# imu.net
KiCad netlist of a schematic drawn in EasyEDA Pro
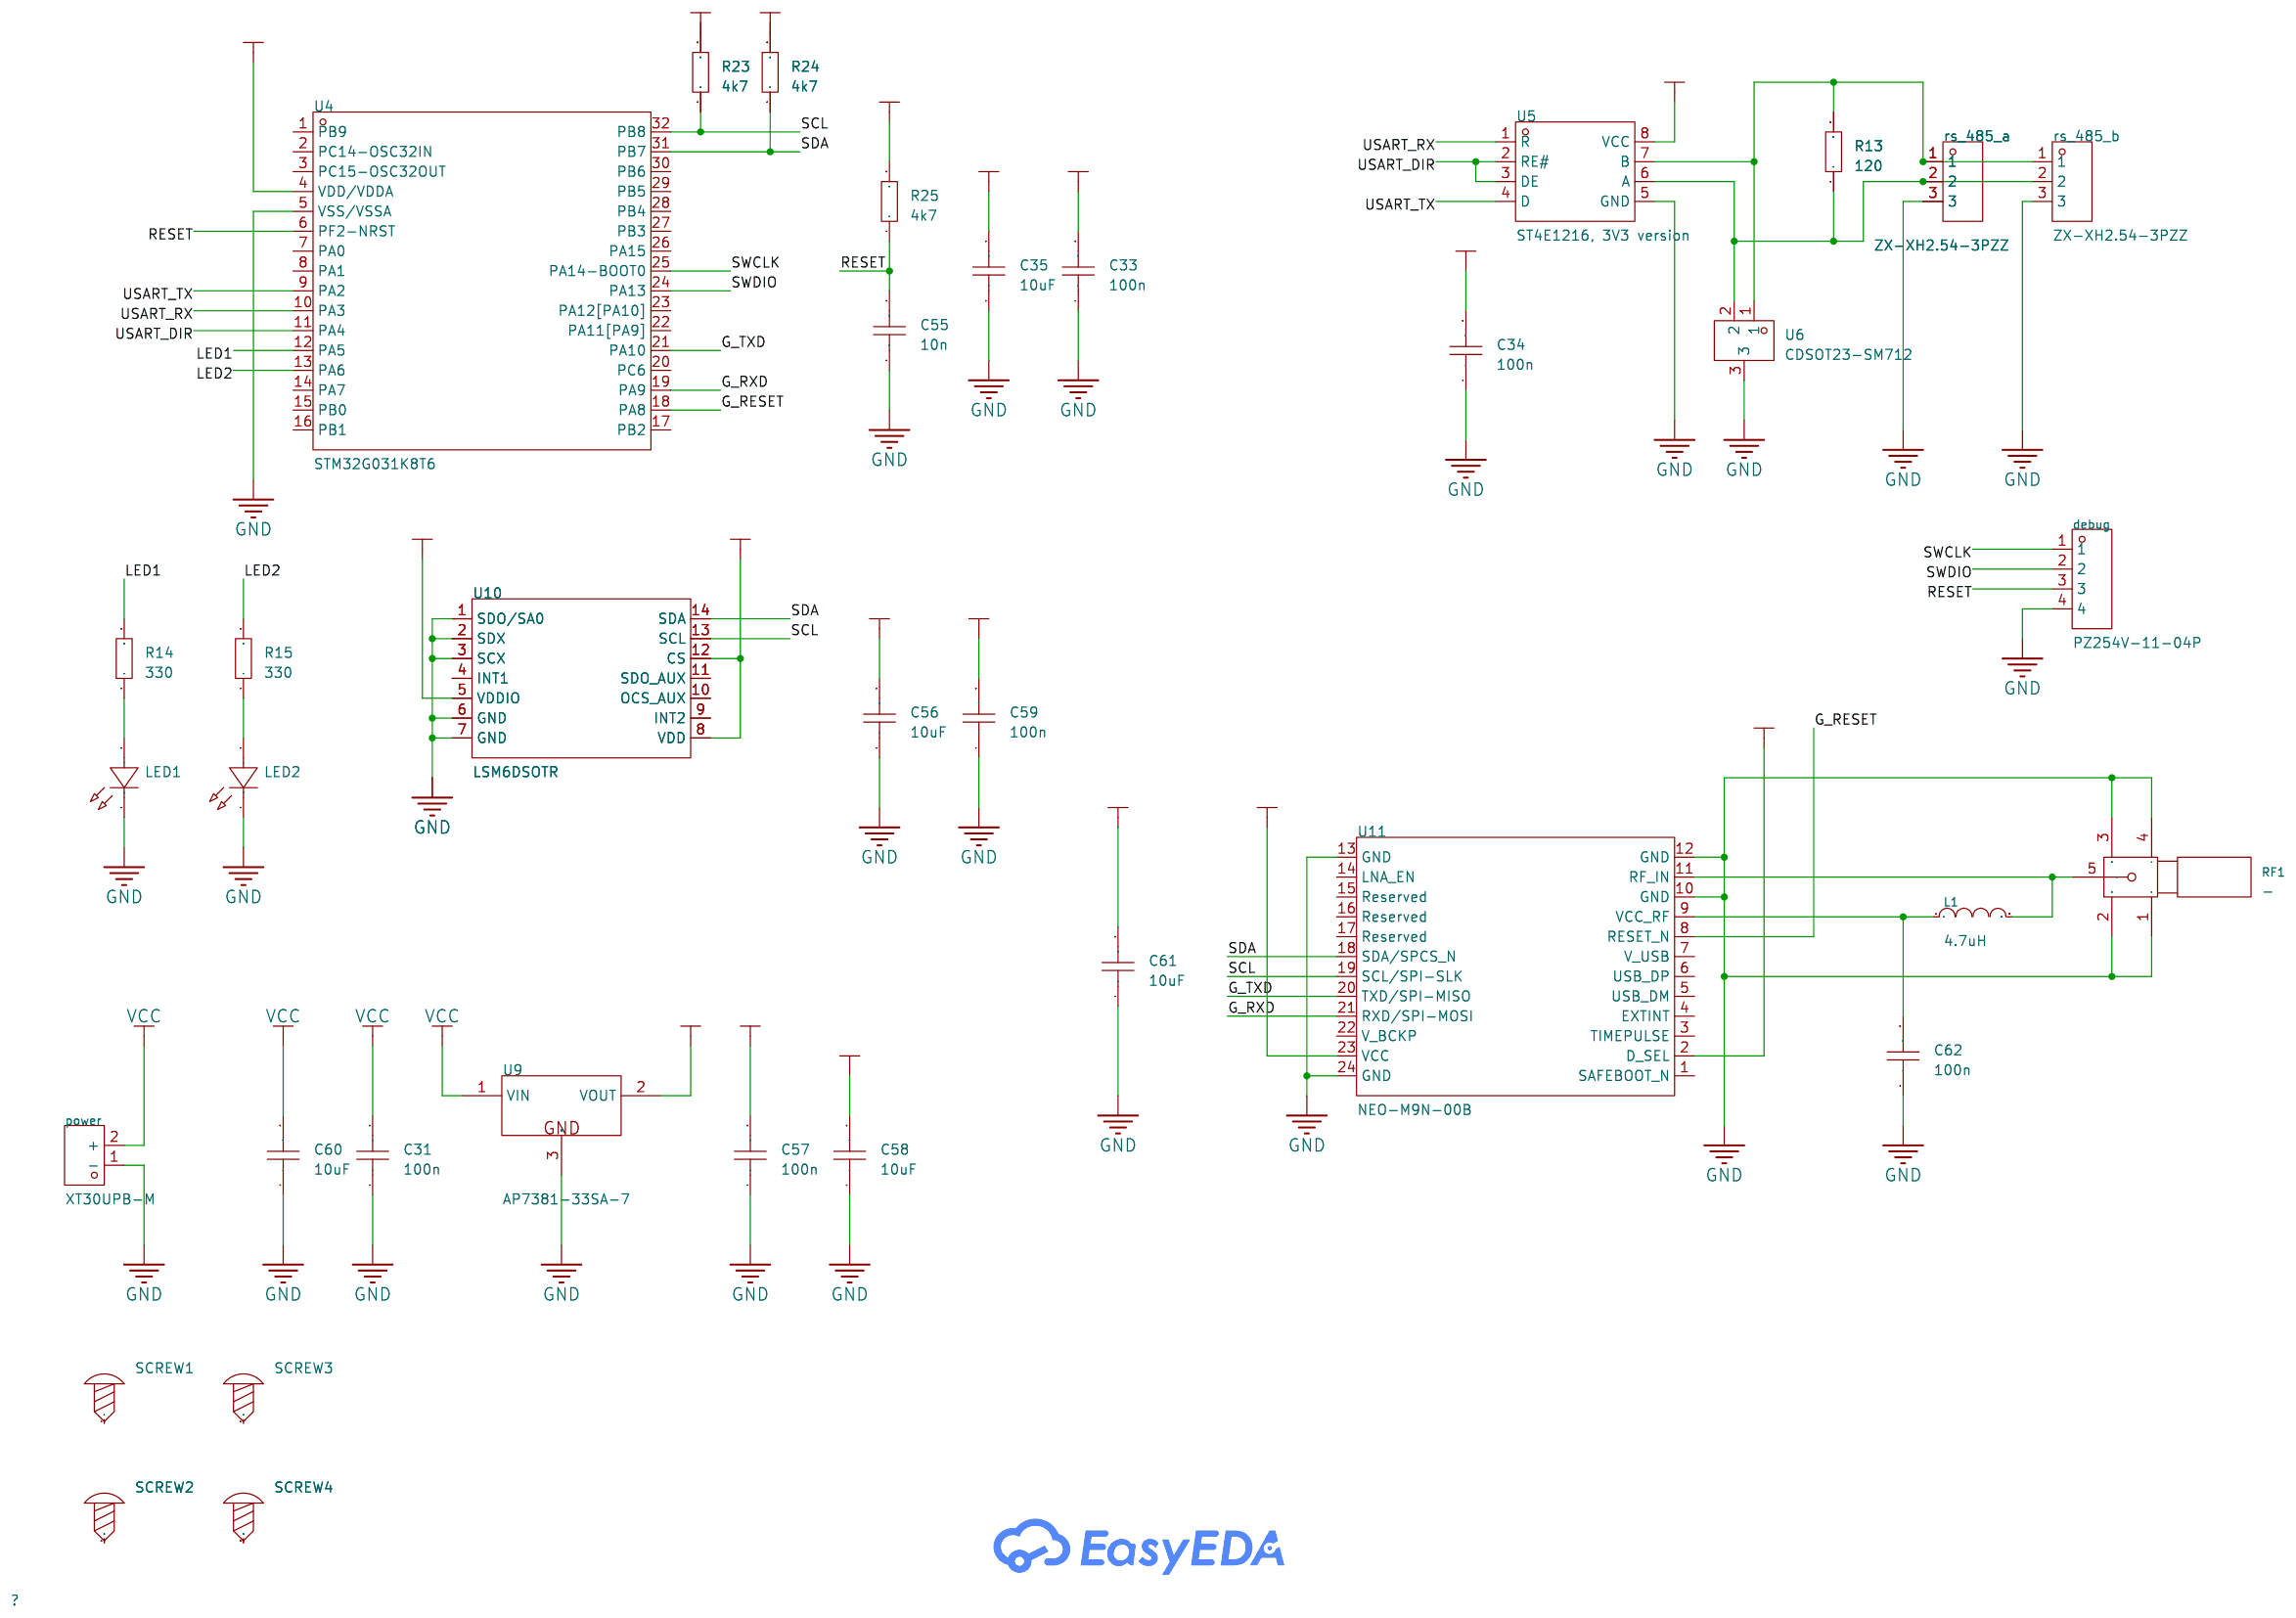
[diagram p0: schematic sheet]

(export (version "E")
  (design (tool "Eeschema 10.0.6"))
  (components
    (comp (ref "C31")
      (value "10uF")
      (footprint "easyedapro:C0805")
      (description "Capacitance:10uF Tolerance:±10% Tolerance:±10% Voltage Rating:25V Temperature Coefficient:X5R")
      (fields
        (field (name "Manufacturer Part") "CL21A106KAYNNNE")
        (field (name "Manufacturer") "SAMSUNG(三星)")
      )
      (libsource (lib "easyedapro") (part "CL21A106KAYNNNE"))
    )
    (comp (ref "C33")
      (value "10uF")
      (footprint "easyedapro:C0805")
      (description "Capacitance:10uF Tolerance:±10% Tolerance:±10% Voltage Rating:25V Temperature Coefficient:X5R")
      (fields
        (field (name "Manufacturer Part") "CL21A106KAYNNNE")
        (field (name "Manufacturer") "SAMSUNG(三星)")
      )
      (libsource (lib "easyedapro") (part "CL21A106KAYNNNE"))
    )
    (comp (ref "C34")
      (value "10uF")
      (footprint "easyedapro:C0805")
      (description "Capacitance:10uF Tolerance:±10% Tolerance:±10% Voltage Rating:25V Temperature Coefficient:X5R")
      (fields
        (field (name "Manufacturer Part") "CL21A106KAYNNNE")
        (field (name "Manufacturer") "SAMSUNG(三星)")
      )
      (libsource (lib "easyedapro") (part "CL21A106KAYNNNE"))
    )
    (comp (ref "C35")
      (value "10uF")
      (footprint "easyedapro:C0805")
      (description "Capacitance:10uF Tolerance:±10% Tolerance:±10% Voltage Rating:25V Temperature Coefficient:X5R")
      (fields
        (field (name "Manufacturer Part") "CL21A106KAYNNNE")
        (field (name "Manufacturer") "SAMSUNG(三星)")
      )
      (libsource (lib "easyedapro") (part "CL21A106KAYNNNE"))
    )
    (comp (ref "C55")
      (value "10uF")
      (footprint "easyedapro:C0805")
      (description "Capacitance:10uF Tolerance:±10% Tolerance:±10% Voltage Rating:25V Temperature Coefficient:X5R")
      (fields
        (field (name "Manufacturer Part") "CL21A106KAYNNNE")
        (field (name "Manufacturer") "SAMSUNG(三星)")
      )
      (libsource (lib "easyedapro") (part "CL21A106KAYNNNE"))
    )
    (comp (ref "C56")
      (value "10uF")
      (footprint "easyedapro:C0805")
      (description "Capacitance:10uF Tolerance:±10% Tolerance:±10% Voltage Rating:25V Temperature Coefficient:X5R")
      (fields
        (field (name "Manufacturer Part") "CL21A106KAYNNNE")
        (field (name "Manufacturer") "SAMSUNG(三星)")
      )
      (libsource (lib "easyedapro") (part "CL21A106KAYNNNE"))
    )
    (comp (ref "C57")
      (value "10uF")
      (footprint "easyedapro:C0805")
      (description "Capacitance:10uF Tolerance:±10% Tolerance:±10% Voltage Rating:25V Temperature Coefficient:X5R")
      (fields
        (field (name "Manufacturer Part") "CL21A106KAYNNNE")
        (field (name "Manufacturer") "SAMSUNG(三星)")
      )
      (libsource (lib "easyedapro") (part "CL21A106KAYNNNE"))
    )
    (comp (ref "C58")
      (value "10uF")
      (footprint "easyedapro:C0805")
      (description "Capacitance:10uF Tolerance:±10% Tolerance:±10% Voltage Rating:25V Temperature Coefficient:X5R")
      (fields
        (field (name "Manufacturer Part") "CL21A106KAYNNNE")
        (field (name "Manufacturer") "SAMSUNG(三星)")
      )
      (libsource (lib "easyedapro") (part "CL21A106KAYNNNE"))
    )
    (comp (ref "C59")
      (value "10uF")
      (footprint "easyedapro:C0805")
      (description "Capacitance:10uF Tolerance:±10% Tolerance:±10% Voltage Rating:25V Temperature Coefficient:X5R")
      (fields
        (field (name "Manufacturer Part") "CL21A106KAYNNNE")
        (field (name "Manufacturer") "SAMSUNG(三星)")
      )
      (libsource (lib "easyedapro") (part "CL21A106KAYNNNE"))
    )
    (comp (ref "C60")
      (value "10uF")
      (footprint "easyedapro:C0805")
      (description "Capacitance:10uF Tolerance:±10% Tolerance:±10% Voltage Rating:25V Temperature Coefficient:X5R")
      (fields
        (field (name "Manufacturer Part") "CL21A106KAYNNNE")
        (field (name "Manufacturer") "SAMSUNG(三星)")
      )
      (libsource (lib "easyedapro") (part "CL21A106KAYNNNE"))
    )
    (comp (ref "C61")
      (value "10uF")
      (footprint "easyedapro:C0805")
      (description "Capacitance:10uF Tolerance:±10% Tolerance:±10% Voltage Rating:25V Temperature Coefficient:X5R")
      (fields
        (field (name "Manufacturer Part") "CL21A106KAYNNNE")
        (field (name "Manufacturer") "SAMSUNG(三星)")
      )
      (libsource (lib "easyedapro") (part "CL21A106KAYNNNE"))
    )
    (comp (ref "C62")
      (value "10uF")
      (footprint "easyedapro:C0805")
      (description "Capacitance:10uF Tolerance:±10% Tolerance:±10% Voltage Rating:25V Temperature Coefficient:X5R")
      (fields
        (field (name "Manufacturer Part") "CL21A106KAYNNNE")
        (field (name "Manufacturer") "SAMSUNG(三星)")
      )
      (libsource (lib "easyedapro") (part "CL21A106KAYNNNE"))
    )
    (comp (ref "debug")
      (value "PZ254V-11-04P")
      (footprint "easyedapro:HDR-TH_4P-P2.54-V-M")
      (fields (field (name "Manufacturer") "XFCN(兴飞)"))
      (libsource (lib "easyedapro") (part "PZ254V-11-04P_C2691448"))
    )
    (comp (ref "L1")
      (value "4.7uH")
      (footprint "easyedapro:L0805")
      (fields (field (name "Manufacturer Part") "LQM21PN4R7MGRD") (field (name "Manufacturer") "muRata(村田)"))
      (libsource (lib "easyedapro") (part "LQM21PN4R7MGRD"))
    )
    (comp (ref "LED1")
      (value "P2-1206RTCS2-0.9T-F")
      (footprint "easyedapro:LED-SMD_L3.2-W1.6-P2-1206RTCS2-0.9T-F")
      (fields (field (name "Manufacturer") "TUOZHAN(拓展光电)"))
      (libsource (lib "easyedapro") (part "P2-1206RTCS2-0.9T-F"))
    )
    (comp (ref "LED2")
      (value "P2-1206RTCS2-0.9T-F")
      (footprint "easyedapro:LED-SMD_L3.2-W1.6-P2-1206RTCS2-0.9T-F")
      (fields (field (name "Manufacturer") "TUOZHAN(拓展光电)"))
      (libsource (lib "easyedapro") (part "P2-1206RTCS2-0.9T-F"))
    )
    (comp (ref "power")
      (value "XT30UPB-M")
      (footprint "easyedapro:CONN-TH_XT30UPB-M")
      (fields (field (name "Manufacturer") "AMASS(艾迈斯)"))
      (libsource (lib "easyedapro") (part "XT30UPB-M"))
    )
    (comp (ref "R13")
      (value "10kΩ")
      (footprint "easyedapro:R0805")
      (fields
        (field (name "Manufacturer Part") "0805W8F1002T5E")
        (field (name "Manufacturer") "UNI-ROYAL(厚声)")
      )
      (libsource (lib "easyedapro") (part "0805W8F1002T5E"))
    )
    (comp (ref "R14")
      (value "10kΩ")
      (footprint "easyedapro:R0805")
      (fields
        (field (name "Manufacturer Part") "0805W8F1002T5E")
        (field (name "Manufacturer") "UNI-ROYAL(厚声)")
      )
      (libsource (lib "easyedapro") (part "0805W8F1002T5E"))
    )
    (comp (ref "R15")
      (value "10kΩ")
      (footprint "easyedapro:R0805")
      (fields
        (field (name "Manufacturer Part") "0805W8F1002T5E")
        (field (name "Manufacturer") "UNI-ROYAL(厚声)")
      )
      (libsource (lib "easyedapro") (part "0805W8F1002T5E"))
    )
    (comp (ref "R23")
      (value "10kΩ")
      (footprint "easyedapro:R0805")
      (fields
        (field (name "Manufacturer Part") "0805W8F1002T5E")
        (field (name "Manufacturer") "UNI-ROYAL(厚声)")
      )
      (libsource (lib "easyedapro") (part "0805W8F1002T5E"))
    )
    (comp (ref "R24")
      (value "10kΩ")
      (footprint "easyedapro:R0805")
      (fields
        (field (name "Manufacturer Part") "0805W8F1002T5E")
        (field (name "Manufacturer") "UNI-ROYAL(厚声)")
      )
      (libsource (lib "easyedapro") (part "0805W8F1002T5E"))
    )
    (comp (ref "R25")
      (value "10kΩ")
      (footprint "easyedapro:R0805")
      (fields
        (field (name "Manufacturer Part") "0805W8F1002T5E")
        (field (name "Manufacturer") "UNI-ROYAL(厚声)")
      )
      (libsource (lib "easyedapro") (part "0805W8F1002T5E"))
    )
    (comp (ref "RF1")
      (value "-")
      (footprint "easyedapro:SMA-TH_BWSMA-KWE-Z001")
      (fields
        (field (name "Manufacturer Part") "BWSMA-KWE-Z001")
        (field (name "Manufacturer") "BAT WIRELESS(蝙蝠无线)")
      )
      (libsource (lib "easyedapro") (part "BWSMA-KWE-Z001"))
    )
    (comp (ref "rs_485_a")
      (value "ZX-XH2.54-3PZZ")
      (footprint "easyedapro:CONN-TH_3P-P2.54_2501S-3P")
      (fields (field (name "Manufacturer") "Megastar(兆星)"))
      (libsource (lib "easyedapro") (part "ZX-XH2.54-3PZZ"))
    )
    (comp (ref "rs_485_b")
      (value "ZX-XH2.54-3PZZ")
      (footprint "easyedapro:CONN-TH_3P-P2.54_2501S-3P")
      (fields (field (name "Manufacturer") "Megastar(兆星)"))
      (libsource (lib "easyedapro") (part "ZX-XH2.54-3PZZ"))
    )
    (comp (ref "SCREW1")
      (value "~")
      (footprint "easyedapro:Screw-Hole-M3")
      (libsource (lib "easyedapro") (part "Screw-Hole"))
    )
    (comp (ref "SCREW2")
      (value "~")
      (footprint "easyedapro:Screw-Hole-M3")
      (libsource (lib "easyedapro") (part "Screw-Hole"))
    )
    (comp (ref "SCREW3")
      (value "~")
      (footprint "easyedapro:Screw-Hole-M3")
      (libsource (lib "easyedapro") (part "Screw-Hole"))
    )
    (comp (ref "SCREW4")
      (value "~")
      (footprint "easyedapro:Screw-Hole-M3")
      (libsource (lib "easyedapro") (part "Screw-Hole"))
    )
    (comp (ref "U4")
      (value "STM32G031K8T6")
      (footprint "easyedapro:LQFP-32_L7.0-W7.0-P0.80-LS9.0-BL")
      (fields (field (name "Manufacturer") "ST(意法半导体)"))
      (libsource (lib "easyedapro") (part "STM32G031K8T6"))
    )
    (comp (ref "U5")
      (value "ST4E1216, 3V3 version")
      (footprint "easyedapro:NSOIC-8_L4.9-W3.9-P1.27-LS6.1-BL")
      (fields (field (name "Manufacturer") "TI(德州仪器)"))
      (libsource (lib "easyedapro") (part "THVD1510DR"))
    )
    (comp (ref "U6")
      (value "CDSOT23-SM712")
      (footprint "easyedapro:SOT-23-3_L2.9-W1.3-P0.95-LS2.4-BR")
      (fields (field (name "Manufacturer") "TECH PUBLIC(台舟)"))
      (libsource (lib "easyedapro") (part "CDSOT23-SM712_C5122012"))
    )
    (comp (ref "U9")
      (value "AP7381-33SA-7")
      (footprint "easyedapro:SOT-23-3_L2.9-W1.3-P1.90-LS2.4-BR")
      (fields (field (name "Manufacturer") "DIODES(美台)"))
      (libsource (lib "easyedapro") (part "AP7381-33SA-7"))
    )
    (comp (ref "U10")
      (value "LSM6DSOTR")
      (footprint "easyedapro:LGA-14_L3.0-W2.5-P0.50-TL")
      (fields (field (name "Manufacturer") "ST(意法半导体)"))
      (libsource (lib "easyedapro") (part "LSM6DSOTR"))
    )
    (comp (ref "U11")
      (value "NEO-M9N-00B")
      (footprint "easyedapro:GPSM-SMD_24P-L16.0-W12.2-P1.10-BL")
      (fields (field (name "Manufacturer") "U-BLOX"))
      (libsource (lib "easyedapro") (part "NEO-M9N-00B"))
    )
  )
  (nets
    (net (code "1") (name "+3V3") (class "Default")
      (node (ref "C33") (pin "2") (pinfunction "2_2") (pintype "unspecified"))
      (node (ref "C34") (pin "2") (pinfunction "2_2") (pintype "unspecified"))
      (node (ref "C35") (pin "2") (pinfunction "2_2") (pintype "unspecified"))
      (node (ref "C56") (pin "2") (pinfunction "2_2") (pintype "unspecified"))
      (node (ref "C57") (pin "2") (pinfunction "2_2") (pintype "unspecified"))
      (node (ref "C58") (pin "2") (pinfunction "2_2") (pintype "unspecified"))
      (node (ref "C59") (pin "2") (pinfunction "2_2") (pintype "unspecified"))
      (node (ref "C61") (pin "2") (pinfunction "2_2") (pintype "unspecified"))
      (node (ref "R23") (pin "2") (pinfunction "2_2") (pintype "input"))
      (node (ref "R24") (pin "2") (pinfunction "2_2") (pintype "input"))
      (node (ref "R25") (pin "2") (pinfunction "2_2") (pintype "input"))
      (node (ref "U10") (pin "12") (pinfunction "CS_12") (pintype "unspecified"))
      (node (ref "U10") (pin "5") (pinfunction "VDDIO_5") (pintype "unspecified"))
      (node (ref "U10") (pin "8") (pinfunction "VDD_8") (pintype "unspecified"))
      (node (ref "U11") (pin "2") (pinfunction "D_SEL_2") (pintype "unspecified"))
      (node (ref "U11") (pin "23") (pinfunction "VCC_23") (pintype "unspecified"))
      (node (ref "U4") (pin "4") (pinfunction "VDD/VDDA_4") (pintype "unspecified"))
      (node (ref "U5") (pin "8") (pinfunction "VCC_8") (pintype "unspecified"))
      (node (ref "U9") (pin "2") (pinfunction "VOUT_2") (pintype "unspecified"))
    )
    (net (code "2") (name "/G_RESET") (class "Default")
      (node (ref "U11") (pin "8") (pinfunction "RESET_N_8") (pintype "unspecified"))
      (node (ref "U4") (pin "18") (pinfunction "PA8_18") (pintype "unspecified"))
    )
    (net (code "3") (name "/G_RXD") (class "Default")
      (node (ref "U11") (pin "21") (pinfunction "RXD/SPI-MOSI_21") (pintype "unspecified"))
      (node (ref "U4") (pin "19") (pinfunction "PA9_19") (pintype "unspecified"))
    )
    (net (code "4") (name "/G_TXD") (class "Default")
      (node (ref "U11") (pin "20") (pinfunction "TXD/SPI-MISO_20") (pintype "unspecified"))
      (node (ref "U4") (pin "21") (pinfunction "PA10_21") (pintype "unspecified"))
    )
    (net (code "5") (name "/LED1") (class "Default")
      (node (ref "R14") (pin "2") (pinfunction "2_2") (pintype "input"))
      (node (ref "U4") (pin "12") (pinfunction "PA5_12") (pintype "unspecified"))
    )
    (net (code "6") (name "/LED2") (class "Default")
      (node (ref "R15") (pin "2") (pinfunction "2_2") (pintype "input"))
      (node (ref "U4") (pin "13") (pinfunction "PA6_13") (pintype "unspecified"))
    )
    (net (code "7") (name "/RESET") (class "Default")
      (node (ref "C55") (pin "2") (pinfunction "2_2") (pintype "unspecified"))
      (node (ref "R25") (pin "1") (pinfunction "1_1") (pintype "input"))
      (node (ref "U4") (pin "6") (pinfunction "PF2-NRST_6") (pintype "unspecified"))
      (node (ref "debug") (pin "3") (pinfunction "3_3") (pintype "input"))
    )
    (net (code "8") (name "/SCL") (class "Default")
      (node (ref "R23") (pin "1") (pinfunction "1_1") (pintype "input"))
      (node (ref "U10") (pin "13") (pinfunction "SCL_13") (pintype "unspecified"))
      (node (ref "U11") (pin "19") (pinfunction "SCL/SPI-SLK_19") (pintype "unspecified"))
      (node (ref "U4") (pin "32") (pinfunction "PB8_32") (pintype "unspecified"))
    )
    (net (code "9") (name "/SDA") (class "Default")
      (node (ref "R24") (pin "1") (pinfunction "1_1") (pintype "input"))
      (node (ref "U10") (pin "14") (pinfunction "SDA_14") (pintype "unspecified"))
      (node (ref "U11") (pin "18") (pinfunction "SDA/SPCS_N_18") (pintype "unspecified"))
      (node (ref "U4") (pin "31") (pinfunction "PB7_31") (pintype "unspecified"))
    )
    (net (code "10") (name "/SWCLK") (class "Default")
      (node (ref "U4") (pin "25") (pinfunction "PA14-BOOT0_25") (pintype "unspecified"))
      (node (ref "debug") (pin "1") (pinfunction "1_1") (pintype "input"))
    )
    (net (code "11") (name "/SWDIO") (class "Default")
      (node (ref "U4") (pin "24") (pinfunction "PA13_24") (pintype "unspecified"))
      (node (ref "debug") (pin "2") (pinfunction "2_2") (pintype "input"))
    )
    (net (code "12") (name "/USART_DIR") (class "Default")
      (node (ref "U4") (pin "11") (pinfunction "PA4_11") (pintype "unspecified"))
      (node (ref "U5") (pin "2") (pinfunction "RE#_2") (pintype "unspecified"))
      (node (ref "U5") (pin "3") (pinfunction "DE_3") (pintype "unspecified"))
    )
    (net (code "13") (name "/USART_RX") (class "Default")
      (node (ref "U4") (pin "10") (pinfunction "PA3_10") (pintype "unspecified"))
      (node (ref "U5") (pin "1") (pinfunction "R_1") (pintype "unspecified"))
    )
    (net (code "14") (name "/USART_TX") (class "Default")
      (node (ref "U4") (pin "9") (pinfunction "PA2_9") (pintype "unspecified"))
      (node (ref "U5") (pin "4") (pinfunction "D_4") (pintype "unspecified"))
    )
    (net (code "15") (name "GND") (class "Default")
      (node (ref "C31") (pin "1") (pinfunction "1_1") (pintype "unspecified"))
      (node (ref "C33") (pin "1") (pinfunction "1_1") (pintype "unspecified"))
      (node (ref "C34") (pin "1") (pinfunction "1_1") (pintype "unspecified"))
      (node (ref "C35") (pin "1") (pinfunction "1_1") (pintype "unspecified"))
      (node (ref "C55") (pin "1") (pinfunction "1_1") (pintype "unspecified"))
      (node (ref "C56") (pin "1") (pinfunction "1_1") (pintype "unspecified"))
      (node (ref "C57") (pin "1") (pinfunction "1_1") (pintype "unspecified"))
      (node (ref "C58") (pin "1") (pinfunction "1_1") (pintype "unspecified"))
      (node (ref "C59") (pin "1") (pinfunction "1_1") (pintype "unspecified"))
      (node (ref "C60") (pin "1") (pinfunction "1_1") (pintype "unspecified"))
      (node (ref "C61") (pin "1") (pinfunction "1_1") (pintype "unspecified"))
      (node (ref "C62") (pin "1") (pinfunction "1_1") (pintype "unspecified"))
      (node (ref "LED1") (pin "1") (pinfunction "C_1") (pintype "unspecified"))
      (node (ref "LED2") (pin "1") (pinfunction "C_1") (pintype "unspecified"))
      (node (ref "RF1") (pin "1") (pinfunction "1_1") (pintype "input"))
      (node (ref "RF1") (pin "2") (pinfunction "2_2") (pintype "input"))
      (node (ref "RF1") (pin "3") (pinfunction "3_3") (pintype "input"))
      (node (ref "RF1") (pin "4") (pinfunction "4_4") (pintype "input"))
      (node (ref "U10") (pin "1") (pinfunction "SDO/SA0_1") (pintype "unspecified"))
      (node (ref "U10") (pin "2") (pinfunction "SDX_2") (pintype "unspecified"))
      (node (ref "U10") (pin "3") (pinfunction "SCX_3") (pintype "unspecified"))
      (node (ref "U10") (pin "6") (pinfunction "GND_6") (pintype "unspecified"))
      (node (ref "U10") (pin "7") (pinfunction "GND_7") (pintype "unspecified"))
      (node (ref "U11") (pin "10") (pinfunction "GND_10") (pintype "unspecified"))
      (node (ref "U11") (pin "12") (pinfunction "GND_12") (pintype "unspecified"))
      (node (ref "U11") (pin "13") (pinfunction "GND_13") (pintype "unspecified"))
      (node (ref "U11") (pin "24") (pinfunction "GND_24") (pintype "unspecified"))
      (node (ref "U4") (pin "5") (pinfunction "VSS/VSSA_5") (pintype "unspecified"))
      (node (ref "U5") (pin "5") (pinfunction "GND_5") (pintype "unspecified"))
      (node (ref "U6") (pin "3") (pinfunction "3_3") (pintype "unspecified"))
      (node (ref "U9") (pin "3") (pinfunction "GND_3") (pintype "unspecified"))
      (node (ref "debug") (pin "4") (pinfunction "4_4") (pintype "input"))
      (node (ref "power") (pin "1") (pinfunction "-_1") (pintype "input"))
      (node (ref "rs_485_a") (pin "3") (pinfunction "3_3") (pintype "unspecified"))
      (node (ref "rs_485_b") (pin "3") (pinfunction "3_3") (pintype "unspecified"))
    )
    (net (code "16") (name "Net-(LED1-A)") (class "Default")
      (node (ref "LED1") (pin "2") (pinfunction "A_2") (pintype "unspecified"))
      (node (ref "R14") (pin "1") (pinfunction "1_1") (pintype "input"))
    )
    (net (code "17") (name "Net-(LED2-A)") (class "Default")
      (node (ref "LED2") (pin "2") (pinfunction "A_2") (pintype "unspecified"))
      (node (ref "R15") (pin "1") (pinfunction "1_1") (pintype "input"))
    )
    (net (code "18") (name "Net-(U5-A)") (class "Default")
      (node (ref "R13") (pin "1") (pinfunction "1_1") (pintype "input"))
      (node (ref "U5") (pin "6") (pinfunction "A_6") (pintype "unspecified"))
      (node (ref "U6") (pin "2") (pinfunction "2_2") (pintype "unspecified"))
      (node (ref "rs_485_a") (pin "2") (pinfunction "2_2") (pintype "unspecified"))
      (node (ref "rs_485_b") (pin "2") (pinfunction "2_2") (pintype "unspecified"))
    )
    (net (code "19") (name "Net-(U5-B)") (class "Default")
      (node (ref "R13") (pin "2") (pinfunction "2_2") (pintype "input"))
      (node (ref "U5") (pin "7") (pinfunction "B_7") (pintype "unspecified"))
      (node (ref "U6") (pin "1") (pinfunction "1_1") (pintype "unspecified"))
      (node (ref "rs_485_a") (pin "1") (pinfunction "1_1") (pintype "unspecified"))
      (node (ref "rs_485_b") (pin "1") (pinfunction "1_1") (pintype "unspecified"))
    )
    (net (code "20") (name "Net-(U11-RF_IN)") (class "Default")
      (node (ref "L1") (pin "2") (pinfunction "2_2") (pintype "input"))
      (node (ref "RF1") (pin "5") (pinfunction "5_5") (pintype "input"))
      (node (ref "U11") (pin "11") (pinfunction "RF_IN_11") (pintype "unspecified"))
    )
    (net (code "21") (name "Net-(U11-VCC_RF)") (class "Default")
      (node (ref "C62") (pin "2") (pinfunction "2_2") (pintype "unspecified"))
      (node (ref "L1") (pin "1") (pinfunction "1_1") (pintype "input"))
      (node (ref "U11") (pin "9") (pinfunction "VCC_RF_9") (pintype "unspecified"))
    )
    (net (code "22") (name "VCC") (class "Default")
      (node (ref "C31") (pin "2") (pinfunction "2_2") (pintype "unspecified"))
      (node (ref "C60") (pin "2") (pinfunction "2_2") (pintype "unspecified"))
      (node (ref "U9") (pin "1") (pinfunction "VIN_1") (pintype "unspecified"))
      (node (ref "power") (pin "2") (pinfunction "+_2") (pintype "input"))
    )
    (net (code "23") (name "unconnected-(SCREW1-Pad1)") (class "Default")
      (node (ref "SCREW1") (pin "1") (pinfunction "1_1") (pintype "input"))
    )
    (net (code "24") (name "unconnected-(SCREW2-Pad1)") (class "Default")
      (node (ref "SCREW2") (pin "1") (pinfunction "1_1") (pintype "input"))
    )
    (net (code "25") (name "unconnected-(SCREW3-Pad1)") (class "Default")
      (node (ref "SCREW3") (pin "1") (pinfunction "1_1") (pintype "input"))
    )
    (net (code "26") (name "unconnected-(SCREW4-Pad1)") (class "Default")
      (node (ref "SCREW4") (pin "1") (pinfunction "1_1") (pintype "input"))
    )
    (net (code "27") (name "unconnected-(U4-PA0-Pad7)") (class "Default")
      (node (ref "U4") (pin "7") (pinfunction "PA0_7") (pintype "unspecified"))
    )
    (net (code "28") (name "unconnected-(U4-PA1-Pad8)") (class "Default")
      (node (ref "U4") (pin "8") (pinfunction "PA1_8") (pintype "unspecified"))
    )
    (net (code "29") (name "unconnected-(U4-PA7-Pad14)") (class "Default")
      (node (ref "U4") (pin "14") (pinfunction "PA7_14") (pintype "unspecified"))
    )
    (net (code "30") (name "unconnected-(U4-PA11[PA9]-Pad22)") (class "Default")
      (node (ref "U4") (pin "22") (pinfunction "PA11[PA9]_22") (pintype "unspecified"))
    )
    (net (code "31") (name "unconnected-(U4-PA12[PA10]-Pad23)") (class "Default")
      (node (ref "U4") (pin "23") (pinfunction "PA12[PA10]_23") (pintype "unspecified"))
    )
    (net (code "32") (name "unconnected-(U4-PA15-Pad26)") (class "Default")
      (node (ref "U4") (pin "26") (pinfunction "PA15_26") (pintype "unspecified"))
    )
    (net (code "33") (name "unconnected-(U4-PB0-Pad15)") (class "Default")
      (node (ref "U4") (pin "15") (pinfunction "PB0_15") (pintype "unspecified"))
    )
    (net (code "34") (name "unconnected-(U4-PB1-Pad16)") (class "Default")
      (node (ref "U4") (pin "16") (pinfunction "PB1_16") (pintype "unspecified"))
    )
    (net (code "35") (name "unconnected-(U4-PB2-Pad17)") (class "Default")
      (node (ref "U4") (pin "17") (pinfunction "PB2_17") (pintype "unspecified"))
    )
    (net (code "36") (name "unconnected-(U4-PB3-Pad27)") (class "Default")
      (node (ref "U4") (pin "27") (pinfunction "PB3_27") (pintype "unspecified"))
    )
    (net (code "37") (name "unconnected-(U4-PB4-Pad28)") (class "Default")
      (node (ref "U4") (pin "28") (pinfunction "PB4_28") (pintype "unspecified"))
    )
    (net (code "38") (name "unconnected-(U4-PB5-Pad29)") (class "Default")
      (node (ref "U4") (pin "29") (pinfunction "PB5_29") (pintype "unspecified"))
    )
    (net (code "39") (name "unconnected-(U4-PB6-Pad30)") (class "Default")
      (node (ref "U4") (pin "30") (pinfunction "PB6_30") (pintype "unspecified"))
    )
    (net (code "40") (name "unconnected-(U4-PB9-Pad1)") (class "Default")
      (node (ref "U4") (pin "1") (pinfunction "PB9_1") (pintype "unspecified"))
    )
    (net (code "41") (name "unconnected-(U4-PC6-Pad20)") (class "Default")
      (node (ref "U4") (pin "20") (pinfunction "PC6_20") (pintype "unspecified"))
    )
    (net (code "42") (name "unconnected-(U4-PC14-OSC32IN-Pad2)") (class "Default")
      (node (ref "U4") (pin "2") (pinfunction "PC14-OSC32IN_2") (pintype "unspecified"))
    )
    (net (code "43") (name "unconnected-(U4-PC15-OSC32OUT-Pad3)") (class "Default")
      (node (ref "U4") (pin "3") (pinfunction "PC15-OSC32OUT_3") (pintype "unspecified"))
    )
    (net (code "44") (name "unconnected-(U10-INT1-Pad4)") (class "Default")
      (node (ref "U10") (pin "4") (pinfunction "INT1_4") (pintype "unspecified"))
    )
    (net (code "45") (name "unconnected-(U10-INT2-Pad9)") (class "Default")
      (node (ref "U10") (pin "9") (pinfunction "INT2_9") (pintype "unspecified"))
    )
    (net (code "46") (name "unconnected-(U10-OCS_AUX-Pad10)") (class "Default")
      (node (ref "U10") (pin "10") (pinfunction "OCS_AUX_10") (pintype "unspecified"))
    )
    (net (code "47") (name "unconnected-(U10-SDO_AUX-Pad11)") (class "Default")
      (node (ref "U10") (pin "11") (pinfunction "SDO_AUX_11") (pintype "unspecified"))
    )
    (net (code "48") (name "unconnected-(U11-EXTINT-Pad4)") (class "Default")
      (node (ref "U11") (pin "4") (pinfunction "EXTINT_4") (pintype "unspecified"))
    )
    (net (code "49") (name "unconnected-(U11-LNA_EN-Pad14)") (class "Default")
      (node (ref "U11") (pin "14") (pinfunction "LNA_EN_14") (pintype "unspecified"))
    )
    (net (code "50") (name "unconnected-(U11-Reserved-Pad15)") (class "Default")
      (node (ref "U11") (pin "15") (pinfunction "Reserved_15") (pintype "unspecified"))
    )
    (net (code "51") (name "unconnected-(U11-Reserved-Pad16)") (class "Default")
      (node (ref "U11") (pin "16") (pinfunction "Reserved_16") (pintype "unspecified"))
    )
    (net (code "52") (name "unconnected-(U11-Reserved-Pad17)") (class "Default")
      (node (ref "U11") (pin "17") (pinfunction "Reserved_17") (pintype "unspecified"))
    )
    (net (code "53") (name "unconnected-(U11-SAFEBOOT_N-Pad1)") (class "Default")
      (node (ref "U11") (pin "1") (pinfunction "SAFEBOOT_N_1") (pintype "unspecified"))
    )
    (net (code "54") (name "unconnected-(U11-TIMEPULSE-Pad3)") (class "Default")
      (node (ref "U11") (pin "3") (pinfunction "TIMEPULSE_3") (pintype "unspecified"))
    )
    (net (code "55") (name "unconnected-(U11-USB_DM-Pad5)") (class "Default")
      (node (ref "U11") (pin "5") (pinfunction "USB_DM_5") (pintype "unspecified"))
    )
    (net (code "56") (name "unconnected-(U11-USB_DP-Pad6)") (class "Default")
      (node (ref "U11") (pin "6") (pinfunction "USB_DP_6") (pintype "unspecified"))
    )
    (net (code "57") (name "unconnected-(U11-V_BCKP-Pad22)") (class "Default")
      (node (ref "U11") (pin "22") (pinfunction "V_BCKP_22") (pintype "unspecified"))
    )
    (net (code "58") (name "unconnected-(U11-V_USB-Pad7)") (class "Default")
      (node (ref "U11") (pin "7") (pinfunction "V_USB_7") (pintype "unspecified"))
    )
  )
)
